# PowerBoard1AMp.net
KiCad netlist of a schematic drawn in EAGLE
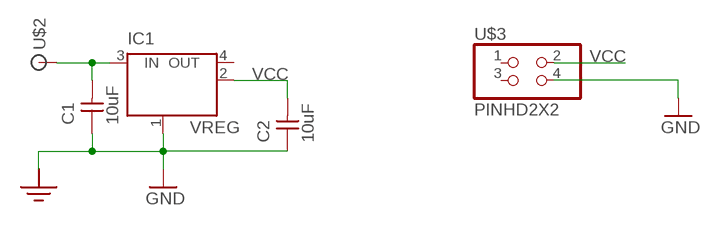
[diagram p0: schematic, sheet 1]

(export (version "E")
  (design (tool "Eeschema 10.0.6"))
  (components
    (comp (ref "C1")
      (value "10uF")
      (footprint "eagle-import:1206")
      (libsource (lib "eagle-import") (part "UNPOLARIZED_CAPACITOR1206"))
    )
    (comp (ref "C2")
      (value "10uF")
      (footprint "eagle-import:1206")
      (libsource (lib "eagle-import") (part "UNPOLARIZED_CAPACITOR1206"))
    )
    (comp (ref "IC1")
      (value "VREG")
      (footprint "eagle-import:SOT223")
      (libsource (lib "eagle-import") (part "MC33269ST-3.3T3"))
    )
    (comp (ref "U$1")
      (value "GND")
      (footprint "eagle-import:PAD.1")
      (libsource (lib "eagle-import") (part "ng_GND"))
    )
    (comp (ref "U$2")
      (value "SIGNAL")
      (footprint "eagle-import:PAD.1")
      (libsource (lib "eagle-import") (part "SIGNAL"))
    )
    (comp (ref "U$3")
      (value "PINHD2X2")
      (footprint "eagle-import:2X02SMD")
      (libsource (lib "eagle-import") (part "PINHD-2X2-SMD"))
    )
  )
  (nets
    (net (code "1") (name "/VCC") (class "Default")
      (node (ref "C2") (pin "2") (pinfunction "2_2") (pintype "passive"))
      (node (ref "IC1") (pin "2") (pinfunction "OUT_2") (pintype "passive"))
      (node (ref "U$3") (pin "2") (pinfunction "2_2") (pintype "passive"))
    )
    (net (code "2") (name "GND") (class "Default")
      (node (ref "C1") (pin "1") (pinfunction "1_1") (pintype "passive"))
      (node (ref "C2") (pin "1") (pinfunction "1_1") (pintype "passive"))
      (node (ref "IC1") (pin "1") (pinfunction "GND/ADJ_1") (pintype "input"))
      (node (ref "U$1") (pin "P$1") (pinfunction "P$1_P$1") (pintype "bidirectional"))
      (node (ref "U$3") (pin "4") (pinfunction "4_4") (pintype "passive"))
    )
    (net (code "3") (name "Net-(IC1-IN)") (class "Default")
      (node (ref "C1") (pin "2") (pinfunction "2_2") (pintype "passive"))
      (node (ref "IC1") (pin "3") (pinfunction "IN_3") (pintype "input"))
      (node (ref "U$2") (pin "P$1") (pinfunction "P$2_P$1") (pintype "bidirectional"))
    )
    (net (code "4") (name "unconnected-(IC1-OUT-Pad4)") (class "Default")
      (node (ref "IC1") (pin "4") (pinfunction "OUT_4") (pintype "passive"))
    )
    (net (code "5") (name "unconnected-(U$3-Pad1)") (class "Default")
      (node (ref "U$3") (pin "1") (pinfunction "1_1") (pintype "passive"))
    )
    (net (code "6") (name "unconnected-(U$3-Pad3)") (class "Default")
      (node (ref "U$3") (pin "3") (pinfunction "3_3") (pintype "passive"))
    )
  )
)
